# CLKB_RS232_port.net
KiCad netlist of a schematic drawn in Altium Designer
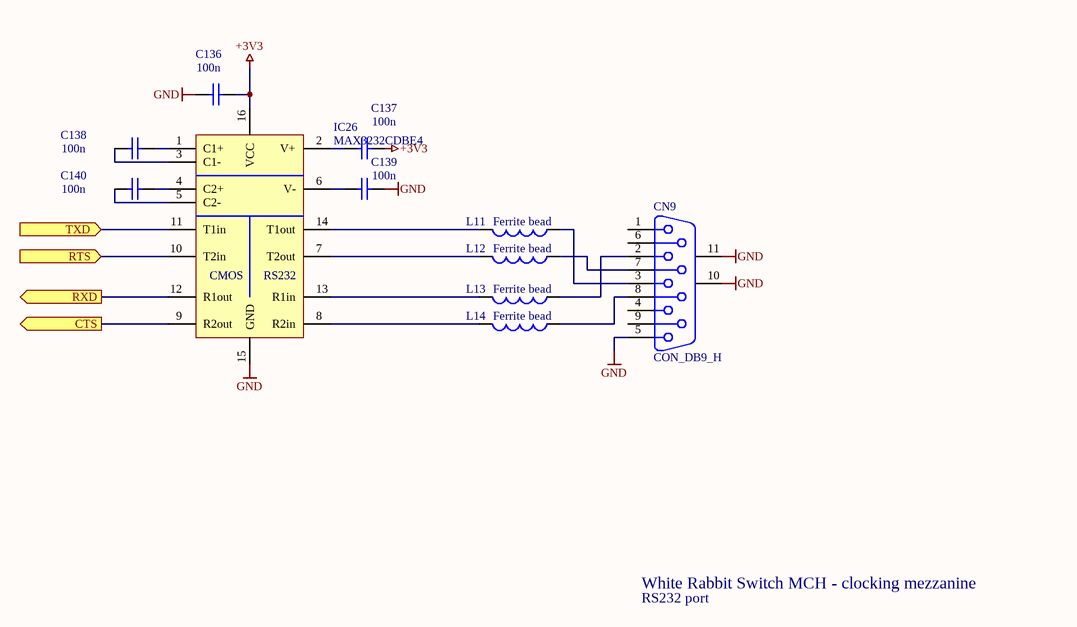
[diagram p0: CLKB_RS232_port.SchDoc]

(export (version "E")
  (design (tool "Eeschema 10.0.6"))
  (components
    (comp (ref "C136")
      (value "100n")
      (footprint "CAPC1608X87N")
      (description "Non-polarised capacitor")
      (fields
        (field (name "PART NUMBER") "CC0603_100NF_50V_10%_X7R")
        (field (name "VOLTAGE") "50V")
        (field (name "AUTHOR") "CERN DEM JLC")
      )
      (libsource (lib "Capacitors") (part "Capacitor - non polarized"))
    )
    (comp (ref "C137")
      (value "100n")
      (footprint "CAPC1608X87N")
      (description "Non-polarised capacitor")
      (fields
        (field (name "PART NUMBER") "CC0603_100NF_50V_10%_X7R")
        (field (name "VOLTAGE") "50V")
        (field (name "AUTHOR") "CERN DEM JLC")
      )
      (libsource (lib "Capacitors") (part "Capacitor - non polarized"))
    )
    (comp (ref "C138")
      (value "100n")
      (footprint "CAPC1608X87N")
      (description "Non-polarised capacitor")
      (fields
        (field (name "PART NUMBER") "CC0603_100NF_50V_10%_X7R")
        (field (name "VOLTAGE") "50V")
        (field (name "AUTHOR") "CERN DEM JLC")
      )
      (libsource (lib "Capacitors") (part "Capacitor - non polarized"))
    )
    (comp (ref "C139")
      (value "100n")
      (footprint "CAPC1608X87N")
      (description "Non-polarised capacitor")
      (fields
        (field (name "PART NUMBER") "CC0603_100NF_50V_10%_X7R")
        (field (name "VOLTAGE") "50V")
        (field (name "AUTHOR") "CERN DEM JLC")
      )
      (libsource (lib "Capacitors") (part "Capacitor - non polarized"))
    )
    (comp (ref "C140")
      (value "100n")
      (footprint "CAPC1608X87N")
      (description "Non-polarised capacitor")
      (fields
        (field (name "PART NUMBER") "CC0603_100NF_50V_10%_X7R")
        (field (name "VOLTAGE") "50V")
        (field (name "AUTHOR") "CERN DEM JLC")
      )
      (libsource (lib "Capacitors") (part "Capacitor - non polarized"))
    )
    (comp (ref "CN9")
      (value "CON_DB9_H")
      (footprint "DSUB_MINI_9")
      (description "Receptacle Assembly, 9 Position, Right Angle")
      (fields (field (name "MANUFACTURER") "Generic Components") (field (name "PUBLISHER") "Altium Limited"))
      (libsource (lib "wr_switch") (part "CON_DB9_H"))
    )
    (comp (ref "IC26")
      (value "MAX3232CDBE4")
      (footprint "Miscellaneous Devices:SSOP16")
      (libsource (lib "wr_switch") (part "IFC_MAX3232"))
    )
    (comp (ref "L11")
      (value "Ferrite bead")
      (footprint "L0603")
      (fields (field (name "PUBLISHER") "Altium Limited"))
      (libsource (lib "Miscellaneous Devices") (part "Inductor"))
    )
    (comp (ref "L12")
      (value "Ferrite bead")
      (footprint "L0603")
      (fields (field (name "PUBLISHER") "Altium Limited"))
      (libsource (lib "Miscellaneous Devices") (part "Inductor"))
    )
    (comp (ref "L13")
      (value "Ferrite bead")
      (footprint "L0603")
      (fields (field (name "PUBLISHER") "Altium Limited"))
      (libsource (lib "Miscellaneous Devices") (part "Inductor"))
    )
    (comp (ref "L14")
      (value "Ferrite bead")
      (footprint "L0603")
      (fields (field (name "PUBLISHER") "Altium Limited"))
      (libsource (lib "Miscellaneous Devices") (part "Inductor"))
    )
  )
  (nets
    (net (code "1") (name "+3V3") (class "Default")
      (node (ref "C136") (pin "2") (pinfunction "2_2") (pintype "passive"))
      (node (ref "C137") (pin "2") (pinfunction "2_2") (pintype "passive"))
      (node (ref "IC26") (pin "16") (pinfunction "VCC_16") (pintype "passive"))
    )
    (net (code "2") (name "/CTS") (class "Default")
      (node (ref "IC26") (pin "9") (pinfunction "R2out_9") (pintype "passive"))
    )
    (net (code "3") (name "/RTS") (class "Default")
      (node (ref "IC26") (pin "10") (pinfunction "T2in_10") (pintype "passive"))
    )
    (net (code "4") (name "/RXD") (class "Default")
      (node (ref "IC26") (pin "12") (pinfunction "R1out_12") (pintype "passive"))
    )
    (net (code "5") (name "/TXD") (class "Default")
      (node (ref "IC26") (pin "11") (pinfunction "T1in_11") (pintype "passive"))
    )
    (net (code "6") (name "GND") (class "Default")
      (node (ref "C136") (pin "1") (pinfunction "1_1") (pintype "passive"))
      (node (ref "C139") (pin "2") (pinfunction "2_2") (pintype "passive"))
      (node (ref "CN9") (pin "10") (pinfunction "MH1_10") (pintype "passive"))
      (node (ref "CN9") (pin "11") (pinfunction "MH2_11") (pintype "passive"))
      (node (ref "CN9") (pin "5") (pinfunction "5_5") (pintype "passive"))
      (node (ref "IC26") (pin "15") (pinfunction "GND_15") (pintype "passive"))
    )
    (net (code "7") (name "Net-(CN9-Pad2)") (class "Default")
      (node (ref "CN9") (pin "2") (pinfunction "2_2") (pintype "passive"))
      (node (ref "L13") (pin "1") (pinfunction "1_1") (pintype "passive"))
    )
    (net (code "8") (name "Net-(CN9-Pad3)") (class "Default")
      (node (ref "CN9") (pin "3") (pinfunction "3_3") (pintype "passive"))
      (node (ref "L11") (pin "1") (pinfunction "1_1") (pintype "passive"))
    )
    (net (code "9") (name "Net-(CN9-Pad7)") (class "Default")
      (node (ref "CN9") (pin "7") (pinfunction "7_7") (pintype "passive"))
      (node (ref "L12") (pin "1") (pinfunction "1_1") (pintype "passive"))
    )
    (net (code "10") (name "Net-(CN9-Pad8)") (class "Default")
      (node (ref "CN9") (pin "8") (pinfunction "8_8") (pintype "passive"))
      (node (ref "L14") (pin "1") (pinfunction "1_1") (pintype "passive"))
    )
    (net (code "11") (name "Net-(IC26-C1+)") (class "Default")
      (node (ref "C138") (pin "2") (pinfunction "2_2") (pintype "passive"))
      (node (ref "IC26") (pin "1") (pinfunction "C1+_1") (pintype "passive"))
    )
    (net (code "12") (name "Net-(IC26-C1-)") (class "Default")
      (node (ref "C138") (pin "1") (pinfunction "1_1") (pintype "passive"))
      (node (ref "IC26") (pin "3") (pinfunction "C1-_3") (pintype "passive"))
    )
    (net (code "13") (name "Net-(IC26-C2+)") (class "Default")
      (node (ref "C140") (pin "2") (pinfunction "2_2") (pintype "passive"))
      (node (ref "IC26") (pin "4") (pinfunction "C2+_4") (pintype "passive"))
    )
    (net (code "14") (name "Net-(IC26-C2-)") (class "Default")
      (node (ref "C140") (pin "1") (pinfunction "1_1") (pintype "passive"))
      (node (ref "IC26") (pin "5") (pinfunction "C2-_5") (pintype "passive"))
    )
    (net (code "15") (name "Net-(IC26-R1in)") (class "Default")
      (node (ref "IC26") (pin "13") (pinfunction "R1in_13") (pintype "passive"))
      (node (ref "L13") (pin "2") (pinfunction "2_2") (pintype "passive"))
    )
    (net (code "16") (name "Net-(IC26-R2in)") (class "Default")
      (node (ref "IC26") (pin "8") (pinfunction "R2in_8") (pintype "passive"))
      (node (ref "L14") (pin "2") (pinfunction "2_2") (pintype "passive"))
    )
    (net (code "17") (name "Net-(IC26-T1out)") (class "Default")
      (node (ref "IC26") (pin "14") (pinfunction "T1out_14") (pintype "passive"))
      (node (ref "L11") (pin "2") (pinfunction "2_2") (pintype "passive"))
    )
    (net (code "18") (name "Net-(IC26-T2out)") (class "Default")
      (node (ref "IC26") (pin "7") (pinfunction "T2out_7") (pintype "passive"))
      (node (ref "L12") (pin "2") (pinfunction "2_2") (pintype "passive"))
    )
    (net (code "19") (name "Net-(IC26-V+)") (class "Default")
      (node (ref "C137") (pin "1") (pinfunction "1_1") (pintype "passive"))
      (node (ref "IC26") (pin "2") (pinfunction "V+_2") (pintype "passive"))
    )
    (net (code "20") (name "Net-(IC26-V-)") (class "Default")
      (node (ref "C139") (pin "1") (pinfunction "1_1") (pintype "passive"))
      (node (ref "IC26") (pin "6") (pinfunction "V-_6") (pintype "passive"))
    )
    (net (code "21") (name "unconnected-(CN9-Pad1)") (class "Default")
      (node (ref "CN9") (pin "1") (pinfunction "1_1") (pintype "passive"))
    )
    (net (code "22") (name "unconnected-(CN9-Pad4)") (class "Default")
      (node (ref "CN9") (pin "4") (pinfunction "4_4") (pintype "passive"))
    )
    (net (code "23") (name "unconnected-(CN9-Pad6)") (class "Default")
      (node (ref "CN9") (pin "6") (pinfunction "6_6") (pintype "passive"))
    )
    (net (code "24") (name "unconnected-(CN9-Pad9)") (class "Default")
      (node (ref "CN9") (pin "9") (pinfunction "9_9") (pintype "passive"))
    )
  )
)
